# Adafruit_ESP8266_Feather.net
KiCad netlist of a schematic drawn in EAGLE
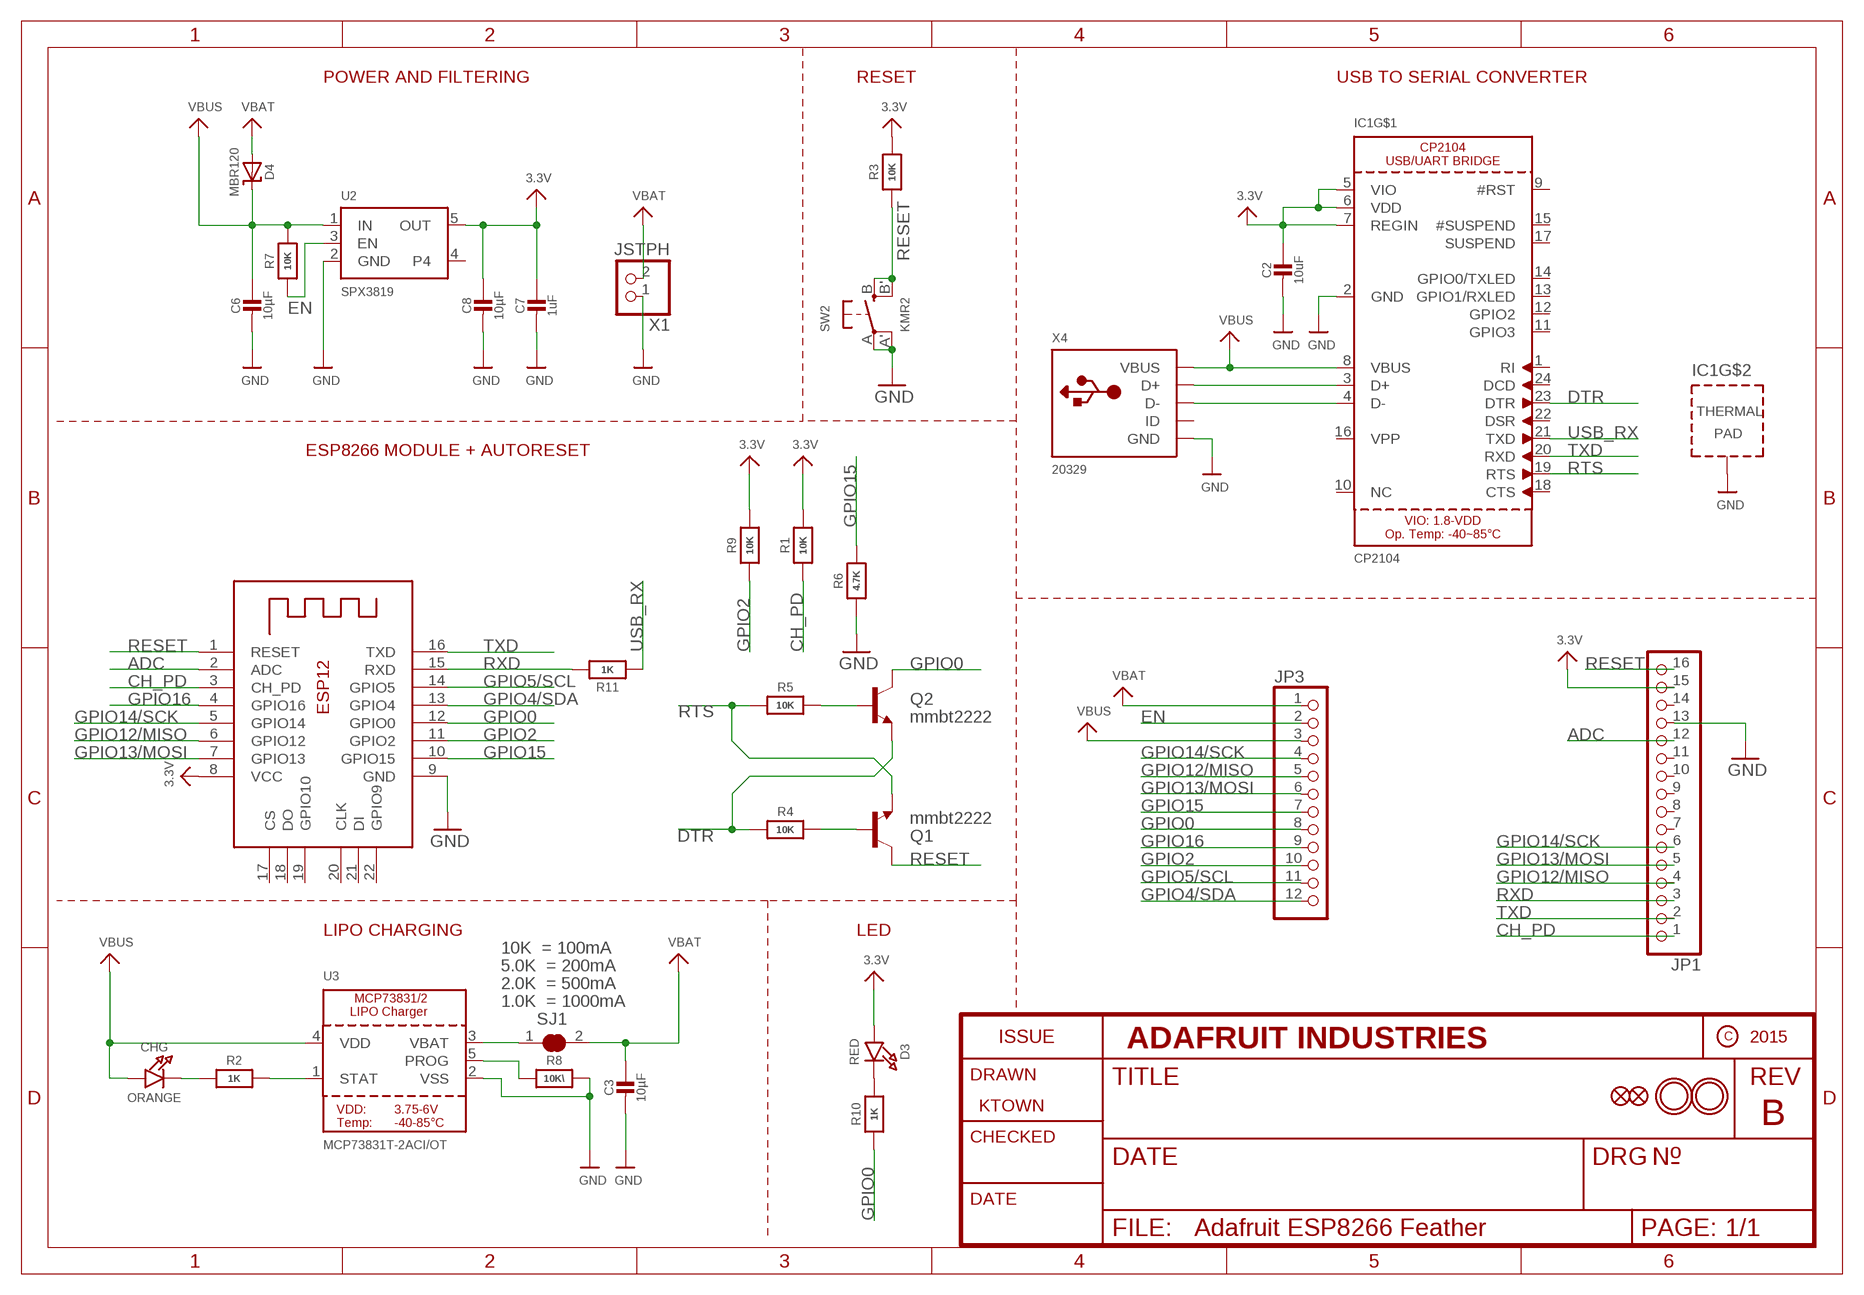
[diagram p0: schematic, sheet 1]

(export (version "E")
  (design (tool "Eeschema 10.0.6"))
  (components
    (comp (ref "C2")
      (value "10uF")
      (footprint "eagle-import:0805-NO")
      (libsource (lib "eagle-import") (part "CAP_CERAMIC0805-NOOUTLINE"))
    )
    (comp (ref "C3")
      (value "10µF")
      (footprint "eagle-import:0805-NO")
      (libsource (lib "eagle-import") (part "CAP_CERAMIC0805-NOOUTLINE"))
    )
    (comp (ref "C6")
      (value "10µF")
      (footprint "eagle-import:0805-NO")
      (libsource (lib "eagle-import") (part "CAP_CERAMIC0805-NOOUTLINE"))
    )
    (comp (ref "C7")
      (value "1uF")
      (footprint "eagle-import:0603-NO")
      (libsource (lib "eagle-import") (part "CAP_CERAMIC0603_NO"))
    )
    (comp (ref "C8")
      (value "10µF")
      (footprint "eagle-import:0805-NO")
      (libsource (lib "eagle-import") (part "CAP_CERAMIC0805-NOOUTLINE"))
    )
    (comp (ref "CHG")
      (value "ORANGE")
      (footprint "eagle-import:CHIPLED_0805_NOOUTLINE")
      (libsource (lib "eagle-import") (part "LED0805_NOOUTLINE"))
    )
    (comp (ref "D3")
      (value "RED")
      (footprint "eagle-import:CHIPLED_0805_NOOUTLINE")
      (libsource (lib "eagle-import") (part "LED0805_NOOUTLINE"))
    )
    (comp (ref "D4")
      (value "MBR120")
      (footprint "eagle-import:SOD-123")
      (libsource (lib "eagle-import") (part "DIODE-SCHOTTKYSOD-123"))
    )
    (comp (ref "IC1")
      (value "CP2104")
      (footprint "eagle-import:QFN24_4MM_SMSC")
      (libsource (lib "eagle-import") (part "CP2104"))
    )
    (comp (ref "JP1")
      (value "HEADER-1X16ROUND")
      (footprint "eagle-import:1X16_ROUND")
      (libsource (lib "eagle-import") (part "HEADER-1X16ROUND"))
    )
    (comp (ref "JP3")
      (value "HEADER-1X12")
      (footprint "eagle-import:1X12_ROUND")
      (libsource (lib "eagle-import") (part "HEADER-1X12"))
    )
    (comp (ref "Q1")
      (value "mmbt2222")
      (footprint "eagle-import:SOT23-3")
      (libsource (lib "eagle-import") (part "TRANSISTOR_NPNSOT23-3"))
    )
    (comp (ref "Q2")
      (value "mmbt2222")
      (footprint "eagle-import:SOT23-3")
      (libsource (lib "eagle-import") (part "TRANSISTOR_NPNSOT23-3"))
    )
    (comp (ref "R1")
      (value "10K")
      (footprint "eagle-import:0603-NO")
      (libsource (lib "eagle-import") (part "RESISTOR_0603_NOOUT"))
    )
    (comp (ref "R2")
      (value "1K")
      (footprint "eagle-import:0603-NO")
      (libsource (lib "eagle-import") (part "RESISTOR_0603_NOOUT"))
    )
    (comp (ref "R3")
      (value "10K")
      (footprint "eagle-import:0603-NO")
      (libsource (lib "eagle-import") (part "RESISTOR_0603_NOOUT"))
    )
    (comp (ref "R4")
      (value "10K")
      (footprint "eagle-import:0603-NO")
      (libsource (lib "eagle-import") (part "RESISTOR_0603_NOOUT"))
    )
    (comp (ref "R5")
      (value "10K")
      (footprint "eagle-import:_0603MP")
      (libsource (lib "eagle-import") (part "RESISTOR_0603MP"))
    )
    (comp (ref "R6")
      (value "4.7K")
      (footprint "eagle-import:0603-NO")
      (libsource (lib "eagle-import") (part "RESISTOR_0603_NOOUT"))
    )
    (comp (ref "R7")
      (value "10K")
      (footprint "eagle-import:0603-NO")
      (libsource (lib "eagle-import") (part "RESISTOR_0603_NOOUT"))
    )
    (comp (ref "R8")
      (value "10K\\")
      (footprint "eagle-import:0603-NO")
      (libsource (lib "eagle-import") (part "RESISTOR_0603_NOOUT"))
    )
    (comp (ref "R9")
      (value "10K")
      (footprint "eagle-import:0603-NO")
      (libsource (lib "eagle-import") (part "RESISTOR_0603_NOOUT"))
    )
    (comp (ref "R10")
      (value "1K")
      (footprint "eagle-import:0603-NO")
      (libsource (lib "eagle-import") (part "RESISTOR_0603_NOOUT"))
    )
    (comp (ref "R11")
      (value "1K")
      (footprint "eagle-import:_0603MP")
      (libsource (lib "eagle-import") (part "RESISTOR_0603MP"))
    )
    (comp (ref "SJ1")
      (value "SOLDERJUMPER_CLOSED")
      (footprint "eagle-import:SOLDERJUMPER_CLOSEDWIRE")
      (libsource (lib "eagle-import") (part "SOLDERJUMPER_CLOSED"))
    )
    (comp (ref "SW2")
      (value "KMR2")
      (footprint "eagle-import:BTN_KMR2_4.6X2.8")
      (libsource (lib "eagle-import") (part "SWITCH_TACT_SMT4.6X2.8"))
    )
    (comp (ref "U$31")
      (value "MOUNTINGHOLE2.5")
      (footprint "eagle-import:MOUNTINGHOLE_2.5_PLATED")
      (libsource (lib "eagle-import") (part "MOUNTINGHOLE2.5"))
    )
    (comp (ref "U$32")
      (value "MOUNTINGHOLE2.5")
      (footprint "eagle-import:MOUNTINGHOLE_2.5_PLATED")
      (libsource (lib "eagle-import") (part "MOUNTINGHOLE2.5"))
    )
    (comp (ref "U$34")
      (value "FIDUCIAL\"\"")
      (footprint "eagle-import:FIDUCIAL_1MM")
      (libsource (lib "eagle-import") (part "FIDUCIAL{dblquote}{dblquote}"))
    )
    (comp (ref "U$35")
      (value "FIDUCIAL\"\"")
      (footprint "eagle-import:FIDUCIAL_1MM")
      (libsource (lib "eagle-import") (part "FIDUCIAL{dblquote}{dblquote}"))
    )
    (comp (ref "U2")
      (value "SPX3819")
      (footprint "eagle-import:SOT23-5")
      (libsource (lib "eagle-import") (part "VREG_SOT23-5"))
    )
    (comp (ref "U3")
      (value "MCP73831T-2ACI/OT")
      (footprint "eagle-import:SOT23-5")
      (libsource (lib "eagle-import") (part "MCP73831/2"))
    )
    (comp (ref "X1")
      (value "JSTPH")
      (footprint "eagle-import:JSTPH2")
      (libsource (lib "eagle-import") (part "CON_JST_PH_2PIN"))
    )
    (comp (ref "X2")
      (value "ESP-12")
      (footprint "eagle-import:ESP-12E")
      (libsource (lib "eagle-import") (part "ESP-12E"))
    )
    (comp (ref "X4")
      (value "20329")
      (footprint "eagle-import:4UCONN_20329_V2")
      (libsource (lib "eagle-import") (part "USB_MICRO_20329_V2"))
    )
  )
  (nets
    (net (code "1") (name "/ADC") (class "Default")
      (node (ref "JP1") (pin "12") (pinfunction "12_12") (pintype "passive"))
      (node (ref "X2") (pin "2") (pinfunction "ADC_2") (pintype "passive"))
    )
    (net (code "2") (name "/CH_PD") (class "Default")
      (node (ref "JP1") (pin "1") (pinfunction "1_1") (pintype "passive"))
      (node (ref "R1") (pin "1") (pinfunction "1_1") (pintype "passive"))
      (node (ref "X2") (pin "3") (pinfunction "CH_PD_3") (pintype "input"))
    )
    (net (code "3") (name "/DTR") (class "Default")
      (node (ref "IC1") (pin "23") (pinfunction "DTR_23") (pintype "output"))
      (node (ref "Q2") (pin "2") (pinfunction "E_2") (pintype "passive"))
      (node (ref "R4") (pin "1") (pinfunction "1_1") (pintype "passive"))
    )
    (net (code "4") (name "/EN") (class "Default")
      (node (ref "JP3") (pin "2") (pinfunction "2_2") (pintype "passive"))
      (node (ref "R7") (pin "1") (pinfunction "1_1") (pintype "passive"))
      (node (ref "U2") (pin "3") (pinfunction "EN_3") (pintype "input"))
    )
    (net (code "5") (name "/GPIO0") (class "Default")
      (node (ref "JP3") (pin "8") (pinfunction "8_8") (pintype "passive"))
      (node (ref "Q2") (pin "3") (pinfunction "C_3") (pintype "passive"))
      (node (ref "R10") (pin "1") (pinfunction "1_1") (pintype "passive"))
      (node (ref "X2") (pin "12") (pinfunction "GPIO0_12") (pintype "bidirectional"))
    )
    (net (code "6") (name "/GPIO2") (class "Default")
      (node (ref "JP3") (pin "10") (pinfunction "10_10") (pintype "passive"))
      (node (ref "R9") (pin "1") (pinfunction "1_1") (pintype "passive"))
      (node (ref "X2") (pin "11") (pinfunction "GPIO2_11") (pintype "bidirectional"))
    )
    (net (code "7") (name "/GPIO4{slash}SDA") (class "Default")
      (node (ref "JP3") (pin "12") (pinfunction "12_12") (pintype "passive"))
      (node (ref "X2") (pin "13") (pinfunction "GPIO4_13") (pintype "bidirectional"))
    )
    (net (code "8") (name "/GPIO5{slash}SCL") (class "Default")
      (node (ref "JP3") (pin "11") (pinfunction "11_11") (pintype "passive"))
      (node (ref "X2") (pin "14") (pinfunction "GPIO5_14") (pintype "bidirectional"))
    )
    (net (code "9") (name "/GPIO12{slash}MISO") (class "Default")
      (node (ref "JP1") (pin "4") (pinfunction "4_4") (pintype "passive"))
      (node (ref "JP3") (pin "5") (pinfunction "5_5") (pintype "passive"))
      (node (ref "X2") (pin "6") (pinfunction "GPIO12_6") (pintype "bidirectional"))
    )
    (net (code "10") (name "/GPIO13{slash}MOSI") (class "Default")
      (node (ref "JP1") (pin "5") (pinfunction "5_5") (pintype "passive"))
      (node (ref "JP3") (pin "6") (pinfunction "6_6") (pintype "passive"))
      (node (ref "X2") (pin "7") (pinfunction "GPIO13_7") (pintype "bidirectional"))
    )
    (net (code "11") (name "/GPIO14{slash}SCK") (class "Default")
      (node (ref "JP1") (pin "6") (pinfunction "6_6") (pintype "passive"))
      (node (ref "JP3") (pin "4") (pinfunction "4_4") (pintype "passive"))
      (node (ref "X2") (pin "5") (pinfunction "GPIO14_5") (pintype "bidirectional"))
    )
    (net (code "12") (name "/GPIO15") (class "Default")
      (node (ref "JP3") (pin "7") (pinfunction "7_7") (pintype "passive"))
      (node (ref "R6") (pin "2") (pinfunction "2_2") (pintype "passive"))
      (node (ref "X2") (pin "10") (pinfunction "GPIO15_10") (pintype "bidirectional"))
    )
    (net (code "13") (name "/GPIO16") (class "Default")
      (node (ref "JP3") (pin "9") (pinfunction "9_9") (pintype "passive"))
      (node (ref "X2") (pin "4") (pinfunction "GPIO16_4") (pintype "bidirectional"))
    )
    (net (code "14") (name "/RESET") (class "Default")
      (node (ref "JP1") (pin "16") (pinfunction "16_16") (pintype "passive"))
      (node (ref "Q1") (pin "3") (pinfunction "C_3") (pintype "passive"))
      (node (ref "R3") (pin "1") (pinfunction "1_1") (pintype "passive"))
      (node (ref "SW2") (pin "B") (pinfunction "S_B") (pintype "passive"))
      (node (ref "SW2") (pin "B'") (pinfunction "S1_B'") (pintype "passive"))
      (node (ref "X2") (pin "1") (pinfunction "RESET_1") (pintype "input"))
    )
    (net (code "15") (name "/RTS") (class "Default")
      (node (ref "IC1") (pin "19") (pinfunction "RTS_19") (pintype "output"))
      (node (ref "Q1") (pin "2") (pinfunction "E_2") (pintype "passive"))
      (node (ref "R5") (pin "1") (pinfunction "1_1") (pintype "passive"))
    )
    (net (code "16") (name "/RXD") (class "Default")
      (node (ref "JP1") (pin "3") (pinfunction "3_3") (pintype "passive"))
      (node (ref "R11") (pin "2") (pinfunction "2_2") (pintype "passive"))
      (node (ref "X2") (pin "15") (pinfunction "RXD_15") (pintype "input"))
    )
    (net (code "17") (name "/TXD") (class "Default")
      (node (ref "IC1") (pin "20") (pinfunction "RXD_20") (pintype "input"))
      (node (ref "JP1") (pin "2") (pinfunction "2_2") (pintype "passive"))
      (node (ref "X2") (pin "16") (pinfunction "TXD_16") (pintype "output"))
    )
    (net (code "18") (name "/USB_RX") (class "Default")
      (node (ref "IC1") (pin "21") (pinfunction "TXD_21") (pintype "output"))
      (node (ref "R11") (pin "1") (pinfunction "1_1") (pintype "passive"))
    )
    (net (code "19") (name "3.3V") (class "Default")
      (node (ref "C2") (pin "1") (pinfunction "1_1") (pintype "passive"))
      (node (ref "C7") (pin "1") (pinfunction "1_1") (pintype "passive"))
      (node (ref "C8") (pin "1") (pinfunction "1_1") (pintype "passive"))
      (node (ref "D3") (pin "A") (pinfunction "A_A") (pintype "passive"))
      (node (ref "IC1") (pin "5") (pinfunction "VIO_5") (pintype "power_in"))
      (node (ref "IC1") (pin "6") (pinfunction "VDD_6") (pintype "power_in"))
      (node (ref "IC1") (pin "7") (pinfunction "REGIN_7") (pintype "power_in"))
      (node (ref "JP1") (pin "15") (pinfunction "15_15") (pintype "passive"))
      (node (ref "R1") (pin "2") (pinfunction "2_2") (pintype "passive"))
      (node (ref "R3") (pin "2") (pinfunction "2_2") (pintype "passive"))
      (node (ref "R9") (pin "2") (pinfunction "2_2") (pintype "passive"))
      (node (ref "U2") (pin "5") (pinfunction "OUT_5") (pintype "power_in"))
      (node (ref "X2") (pin "8") (pinfunction "VCC_8") (pintype "power_in"))
    )
    (net (code "20") (name "GND") (class "Default")
      (node (ref "C2") (pin "2") (pinfunction "2_2") (pintype "passive"))
      (node (ref "C3") (pin "2") (pinfunction "2_2") (pintype "passive"))
      (node (ref "C6") (pin "2") (pinfunction "2_2") (pintype "passive"))
      (node (ref "C7") (pin "2") (pinfunction "2_2") (pintype "passive"))
      (node (ref "C8") (pin "2") (pinfunction "2_2") (pintype "passive"))
      (node (ref "IC1") (pin "2") (pinfunction "GND_2") (pintype "power_in"))
      (node (ref "IC1") (pin "THERM") (pinfunction "TP_THERM") (pintype "power_in"))
      (node (ref "JP1") (pin "13") (pinfunction "13_13") (pintype "passive"))
      (node (ref "R6") (pin "1") (pinfunction "1_1") (pintype "passive"))
      (node (ref "R8") (pin "2") (pinfunction "2_2") (pintype "passive"))
      (node (ref "SW2") (pin "A") (pinfunction "P_A") (pintype "passive"))
      (node (ref "SW2") (pin "A'") (pinfunction "P1_A'") (pintype "passive"))
      (node (ref "U2") (pin "2") (pinfunction "GND_2") (pintype "power_in"))
      (node (ref "U3") (pin "2") (pinfunction "VSS_2") (pintype "power_in"))
      (node (ref "X1") (pin "1") (pinfunction "1_1") (pintype "passive"))
      (node (ref "X2") (pin "9") (pinfunction "GND_9") (pintype "power_in"))
      (node (ref "X4") (pin "BASE@1") (pinfunction "GND_BASE@1") (pintype "power_in"))
      (node (ref "X4") (pin "BASE@2") (pinfunction "GND_BASE@2") (pintype "power_in"))
      (node (ref "X4") (pin "GND") (pinfunction "GND_GND") (pintype "power_in"))
      (node (ref "X4") (pin "SPRT@1") (pinfunction "GND_SPRT@1") (pintype "power_in"))
      (node (ref "X4") (pin "SPRT@2") (pinfunction "GND_SPRT@2") (pintype "power_in"))
      (node (ref "X4") (pin "SPRT@3") (pinfunction "GND_SPRT@3") (pintype "power_in"))
      (node (ref "X4") (pin "SPRT@4") (pinfunction "GND_SPRT@4") (pintype "power_in"))
    )
    (net (code "21") (name "Net-(CHG-PadC)") (class "Default")
      (node (ref "CHG") (pin "C") (pinfunction "C_C") (pintype "passive"))
      (node (ref "R2") (pin "1") (pinfunction "1_1") (pintype "passive"))
    )
    (net (code "22") (name "Net-(D3-PadC)") (class "Default")
      (node (ref "D3") (pin "C") (pinfunction "C_C") (pintype "passive"))
      (node (ref "R10") (pin "2") (pinfunction "2_2") (pintype "passive"))
    )
    (net (code "23") (name "Net-(IC1A-D+)") (class "Default")
      (node (ref "IC1") (pin "3") (pinfunction "D+_3") (pintype "bidirectional"))
      (node (ref "X4") (pin "D+") (pinfunction "D+_D+") (pintype "bidirectional"))
    )
    (net (code "24") (name "Net-(IC1A-D-)") (class "Default")
      (node (ref "IC1") (pin "4") (pinfunction "D-_4") (pintype "bidirectional"))
      (node (ref "X4") (pin "D-") (pinfunction "D-_D-") (pintype "bidirectional"))
    )
    (net (code "25") (name "Net-(Q1-B)") (class "Default")
      (node (ref "Q1") (pin "1") (pinfunction "B_1") (pintype "passive"))
      (node (ref "R4") (pin "2") (pinfunction "2_2") (pintype "passive"))
    )
    (net (code "26") (name "Net-(Q2-B)") (class "Default")
      (node (ref "Q2") (pin "1") (pinfunction "B_1") (pintype "passive"))
      (node (ref "R5") (pin "2") (pinfunction "2_2") (pintype "passive"))
    )
    (net (code "27") (name "Net-(U3-PROG)") (class "Default")
      (node (ref "R8") (pin "1") (pinfunction "1_1") (pintype "passive"))
      (node (ref "U3") (pin "5") (pinfunction "PROG_5") (pintype "input"))
    )
    (net (code "28") (name "Net-(U3-STAT)") (class "Default")
      (node (ref "R2") (pin "2") (pinfunction "2_2") (pintype "passive"))
      (node (ref "U3") (pin "1") (pinfunction "STAT_1") (pintype "output"))
    )
    (net (code "29") (name "Net-(U3-VBAT)") (class "Default")
      (node (ref "SJ1") (pin "1") (pinfunction "1_1") (pintype "passive"))
      (node (ref "U3") (pin "3") (pinfunction "VBAT_3") (pintype "power_in"))
    )
    (net (code "30") (name "VBAT") (class "Default")
      (node (ref "C3") (pin "1") (pinfunction "1_1") (pintype "passive"))
      (node (ref "D4") (pin "A") (pinfunction "A_A") (pintype "passive"))
      (node (ref "JP3") (pin "1") (pinfunction "1_1") (pintype "passive"))
      (node (ref "SJ1") (pin "2") (pinfunction "2_2") (pintype "passive"))
      (node (ref "X1") (pin "2") (pinfunction "2_2") (pintype "passive"))
    )
    (net (code "31") (name "VBUS") (class "Default")
      (node (ref "C6") (pin "1") (pinfunction "1_1") (pintype "passive"))
      (node (ref "CHG") (pin "A") (pinfunction "A_A") (pintype "passive"))
      (node (ref "D4") (pin "C") (pinfunction "C_C") (pintype "passive"))
      (node (ref "IC1") (pin "8") (pinfunction "VBUS_8") (pintype "power_in"))
      (node (ref "JP3") (pin "3") (pinfunction "3_3") (pintype "passive"))
      (node (ref "R7") (pin "2") (pinfunction "2_2") (pintype "passive"))
      (node (ref "U2") (pin "1") (pinfunction "IN_1") (pintype "power_in"))
      (node (ref "U3") (pin "4") (pinfunction "VDD_4") (pintype "power_in"))
      (node (ref "X4") (pin "VBUS") (pinfunction "VBUS_VBUS") (pintype "power_in"))
    )
    (net (code "32") (name "unconnected-(IC1A-#RST-Pad9)") (class "Default")
      (node (ref "IC1") (pin "9") (pinfunction "#RST_9") (pintype "bidirectional"))
    )
    (net (code "33") (name "unconnected-(IC1A-#SUSPEND-Pad15)") (class "Default")
      (node (ref "IC1") (pin "15") (pinfunction "#SUSPEND_15") (pintype "output"))
    )
    (net (code "34") (name "unconnected-(IC1A-CTS-Pad18)") (class "Default")
      (node (ref "IC1") (pin "18") (pinfunction "CTS_18") (pintype "input"))
    )
    (net (code "35") (name "unconnected-(IC1A-DCD-Pad24)") (class "Default")
      (node (ref "IC1") (pin "24") (pinfunction "DCD_24") (pintype "input"))
    )
    (net (code "36") (name "unconnected-(IC1A-DSR-Pad22)") (class "Default")
      (node (ref "IC1") (pin "22") (pinfunction "DSR_22") (pintype "input"))
    )
    (net (code "37") (name "unconnected-(IC1A-GPIO0{slash}TXLED-Pad14)") (class "Default")
      (node (ref "IC1") (pin "14") (pinfunction "GPIO0/TXLED_14") (pintype "bidirectional"))
    )
    (net (code "38") (name "unconnected-(IC1A-GPIO1{slash}RXLED-Pad13)") (class "Default")
      (node (ref "IC1") (pin "13") (pinfunction "GPIO1/RXLED_13") (pintype "bidirectional"))
    )
    (net (code "39") (name "unconnected-(IC1A-GPIO2-Pad12)") (class "Default")
      (node (ref "IC1") (pin "12") (pinfunction "GPIO2_12") (pintype "bidirectional"))
    )
    (net (code "40") (name "unconnected-(IC1A-GPIO3-Pad11)") (class "Default")
      (node (ref "IC1") (pin "11") (pinfunction "GPIO3_11") (pintype "bidirectional"))
    )
    (net (code "41") (name "unconnected-(IC1A-NC-Pad10)") (class "Default")
      (node (ref "IC1") (pin "10") (pinfunction "NC_10") (pintype "no_connect"))
    )
    (net (code "42") (name "unconnected-(IC1A-RI-Pad1)") (class "Default")
      (node (ref "IC1") (pin "1") (pinfunction "RI_1") (pintype "input"))
    )
    (net (code "43") (name "unconnected-(IC1A-SUSPEND-Pad17)") (class "Default")
      (node (ref "IC1") (pin "17") (pinfunction "SUSPEND_17") (pintype "output"))
    )
    (net (code "44") (name "unconnected-(IC1A-VPP-Pad16)") (class "Default")
      (node (ref "IC1") (pin "16") (pinfunction "VPP_16") (pintype "bidirectional"))
    )
    (net (code "45") (name "unconnected-(JP1-Pad7)") (class "Default")
      (node (ref "JP1") (pin "7") (pinfunction "7_7") (pintype "passive"))
    )
    (net (code "46") (name "unconnected-(JP1-Pad8)") (class "Default")
      (node (ref "JP1") (pin "8") (pinfunction "8_8") (pintype "passive"))
    )
    (net (code "47") (name "unconnected-(JP1-Pad9)") (class "Default")
      (node (ref "JP1") (pin "9") (pinfunction "9_9") (pintype "passive"))
    )
    (net (code "48") (name "unconnected-(JP1-Pad10)") (class "Default")
      (node (ref "JP1") (pin "10") (pinfunction "10_10") (pintype "passive"))
    )
    (net (code "49") (name "unconnected-(JP1-Pad11)") (class "Default")
      (node (ref "JP1") (pin "11") (pinfunction "11_11") (pintype "passive"))
    )
    (net (code "50") (name "unconnected-(JP1-Pad14)") (class "Default")
      (node (ref "JP1") (pin "14") (pinfunction "14_14") (pintype "passive"))
    )
    (net (code "51") (name "unconnected-(U2-P4-Pad4)") (class "Default")
      (node (ref "U2") (pin "4") (pinfunction "P4_4") (pintype "bidirectional"))
    )
    (net (code "52") (name "unconnected-(X2-CLK-Pad20)") (class "Default")
      (node (ref "X2") (pin "20") (pinfunction "CLK_20") (pintype "bidirectional"))
    )
    (net (code "53") (name "unconnected-(X2-CS-Pad17)") (class "Default")
      (node (ref "X2") (pin "17") (pinfunction "CS_17") (pintype "bidirectional"))
    )
    (net (code "54") (name "unconnected-(X2-DI-Pad21)") (class "Default")
      (node (ref "X2") (pin "21") (pinfunction "DI_21") (pintype "bidirectional"))
    )
    (net (code "55") (name "unconnected-(X2-DO-Pad18)") (class "Default")
      (node (ref "X2") (pin "18") (pinfunction "DO_18") (pintype "bidirectional"))
    )
    (net (code "56") (name "unconnected-(X2-GPIO9-Pad22)") (class "Default")
      (node (ref "X2") (pin "22") (pinfunction "GPIO9_22") (pintype "bidirectional"))
    )
    (net (code "57") (name "unconnected-(X2-GPIO10-Pad19)") (class "Default")
      (node (ref "X2") (pin "19") (pinfunction "GPIO10_19") (pintype "bidirectional"))
    )
    (net (code "58") (name "unconnected-(X4-PadID)") (class "Default")
      (node (ref "X4") (pin "ID") (pinfunction "ID_ID") (pintype "bidirectional"))
    )
  )
)
